# ui.net
KiCad netlist of a schematic drawn in EAGLE
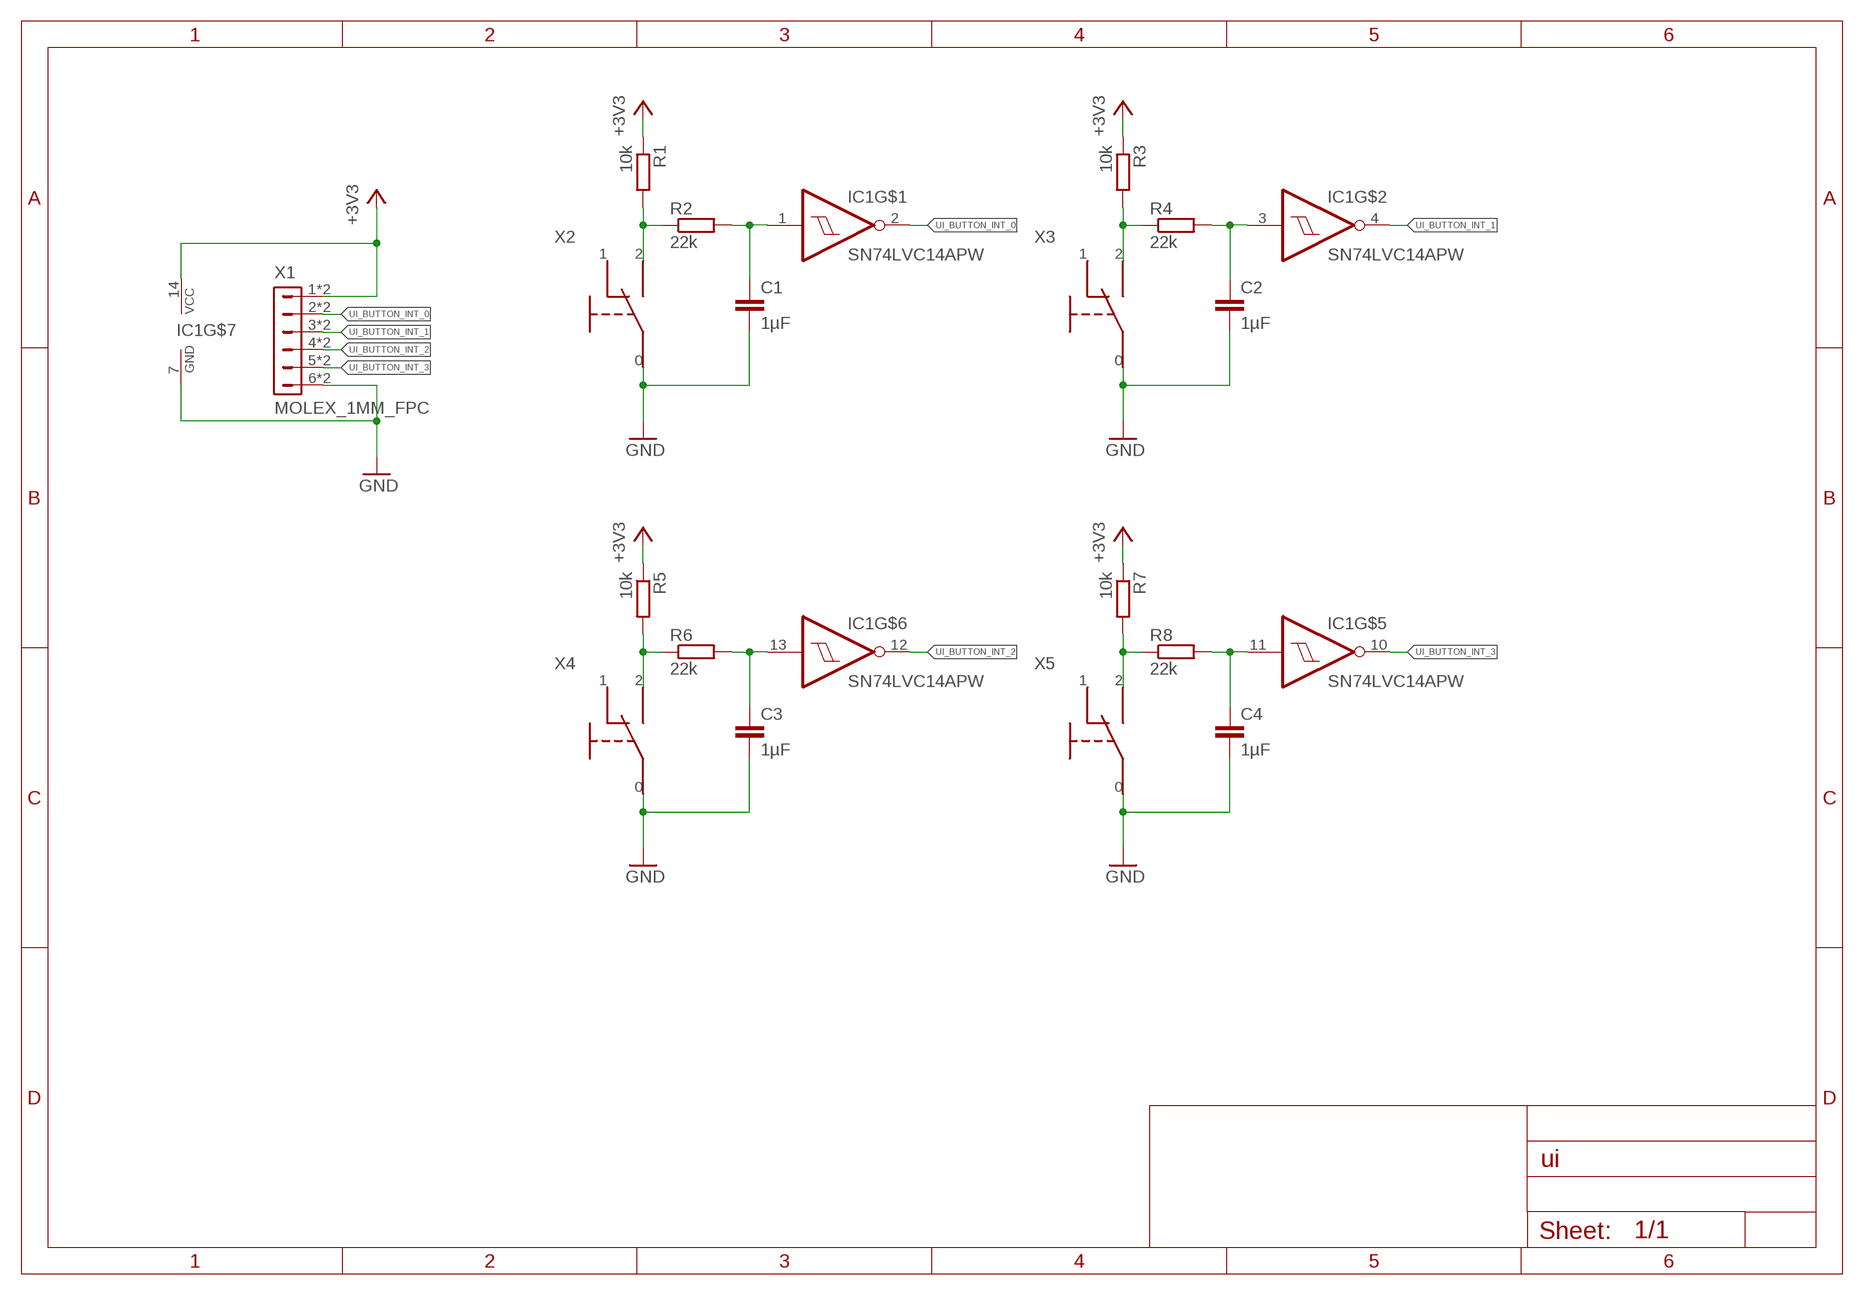
[diagram p0: schematic, sheet 1]

(export (version "E")
  (design (tool "Eeschema 10.0.6"))
  (components
    (comp (ref "C1")
      (value "1µF")
      (footprint "eagle-import:C0805")
      (libsource (lib "eagle-import") (part "C-EUC0805"))
    )
    (comp (ref "C2")
      (value "1µF")
      (footprint "eagle-import:C0805")
      (libsource (lib "eagle-import") (part "C-EUC0805"))
    )
    (comp (ref "C3")
      (value "1µF")
      (footprint "eagle-import:C0805")
      (libsource (lib "eagle-import") (part "C-EUC0805"))
    )
    (comp (ref "C4")
      (value "1µF")
      (footprint "eagle-import:C0805")
      (libsource (lib "eagle-import") (part "C-EUC0805"))
    )
    (comp (ref "IC1")
      (value "SN74LVC14APW")
      (footprint "eagle-import:TSSOP14")
      (fields (field (name "OC_MOUSER") "595-SN74LVC14APWR"))
      (libsource (lib "eagle-import") (part "SN74LVC14APW"))
    )
    (comp (ref "R1")
      (value "10k")
      (footprint "eagle-import:R0805")
      (libsource (lib "eagle-import") (part "R-EU_R0805"))
    )
    (comp (ref "R2")
      (value "22k")
      (footprint "eagle-import:R0805")
      (libsource (lib "eagle-import") (part "R-EU_R0805"))
    )
    (comp (ref "R3")
      (value "10k")
      (footprint "eagle-import:R0805")
      (libsource (lib "eagle-import") (part "R-EU_R0805"))
    )
    (comp (ref "R4")
      (value "22k")
      (footprint "eagle-import:R0805")
      (libsource (lib "eagle-import") (part "R-EU_R0805"))
    )
    (comp (ref "R5")
      (value "10k")
      (footprint "eagle-import:R0805")
      (libsource (lib "eagle-import") (part "R-EU_R0805"))
    )
    (comp (ref "R6")
      (value "22k")
      (footprint "eagle-import:R0805")
      (libsource (lib "eagle-import") (part "R-EU_R0805"))
    )
    (comp (ref "R7")
      (value "10k")
      (footprint "eagle-import:R0805")
      (libsource (lib "eagle-import") (part "R-EU_R0805"))
    )
    (comp (ref "R8")
      (value "22k")
      (footprint "eagle-import:R0805")
      (libsource (lib "eagle-import") (part "R-EU_R0805"))
    )
    (comp (ref "X1")
      (value "MOLEX_1MM_FPC")
      (footprint "eagle-import:1MM_FPC_ZIF")
      (libsource (lib "eagle-import") (part "MOLEX_1MM_FPC"))
    )
    (comp (ref "X2")
      (value "PVA2OAH11.7NV2")
      (footprint "eagle-import:BUTTON-2")
      (libsource (lib "eagle-import") (part "PVA2OAH11.7NV2"))
    )
    (comp (ref "X3")
      (value "PVA2OAH11.7NV2")
      (footprint "eagle-import:BUTTON-2")
      (libsource (lib "eagle-import") (part "PVA2OAH11.7NV2"))
    )
    (comp (ref "X4")
      (value "PVA2OAH11.7NV2")
      (footprint "eagle-import:BUTTON-2")
      (libsource (lib "eagle-import") (part "PVA2OAH11.7NV2"))
    )
    (comp (ref "X5")
      (value "PVA2OAH11.7NV2")
      (footprint "eagle-import:BUTTON-2")
      (libsource (lib "eagle-import") (part "PVA2OAH11.7NV2"))
    )
  )
  (nets
    (net (code "1") (name "+3V3") (class "Default")
      (node (ref "IC1") (pin "14") (pinfunction "VCC_14") (pintype "power_in"))
      (node (ref "R1") (pin "1") (pinfunction "1_1") (pintype "passive"))
      (node (ref "R3") (pin "1") (pinfunction "1_1") (pintype "passive"))
      (node (ref "R5") (pin "1") (pinfunction "1_1") (pintype "passive"))
      (node (ref "R7") (pin "1") (pinfunction "1_1") (pintype "passive"))
      (node (ref "X1") (pin "1") (pinfunction "1_1") (pintype "passive"))
      (node (ref "X1") (pin "7") (pinfunction "1_7") (pintype "passive"))
    )
    (net (code "2") (name "GND") (class "Default")
      (node (ref "C1") (pin "2") (pinfunction "2_2") (pintype "passive"))
      (node (ref "C2") (pin "2") (pinfunction "2_2") (pintype "passive"))
      (node (ref "C3") (pin "2") (pinfunction "2_2") (pintype "passive"))
      (node (ref "C4") (pin "2") (pinfunction "2_2") (pintype "passive"))
      (node (ref "IC1") (pin "7") (pinfunction "GND_7") (pintype "power_in"))
      (node (ref "X1") (pin "12") (pinfunction "6_12") (pintype "passive"))
      (node (ref "X1") (pin "6") (pinfunction "6_6") (pintype "passive"))
      (node (ref "X2") (pin "0") (pinfunction "0_0") (pintype "bidirectional"))
      (node (ref "X3") (pin "0") (pinfunction "0_0") (pintype "bidirectional"))
      (node (ref "X4") (pin "0") (pinfunction "0_0") (pintype "bidirectional"))
      (node (ref "X5") (pin "0") (pinfunction "0_0") (pintype "bidirectional"))
    )
    (net (code "3") (name "Net-(IC1A-I)") (class "Default")
      (node (ref "C1") (pin "1") (pinfunction "1_1") (pintype "passive"))
      (node (ref "IC1") (pin "1") (pinfunction "I_1") (pintype "input"))
      (node (ref "R2") (pin "2") (pinfunction "2_2") (pintype "passive"))
    )
    (net (code "4") (name "Net-(IC1B-I)") (class "Default")
      (node (ref "C2") (pin "1") (pinfunction "1_1") (pintype "passive"))
      (node (ref "IC1") (pin "3") (pinfunction "I_3") (pintype "input"))
      (node (ref "R4") (pin "2") (pinfunction "2_2") (pintype "passive"))
    )
    (net (code "5") (name "Net-(IC1E-I)") (class "Default")
      (node (ref "C4") (pin "1") (pinfunction "1_1") (pintype "passive"))
      (node (ref "IC1") (pin "11") (pinfunction "I_11") (pintype "input"))
      (node (ref "R8") (pin "2") (pinfunction "2_2") (pintype "passive"))
    )
    (net (code "6") (name "Net-(IC1F-I)") (class "Default")
      (node (ref "C3") (pin "1") (pinfunction "1_1") (pintype "passive"))
      (node (ref "IC1") (pin "13") (pinfunction "I_13") (pintype "input"))
      (node (ref "R6") (pin "2") (pinfunction "2_2") (pintype "passive"))
    )
    (net (code "7") (name "Net-(R1-Pad2)") (class "Default")
      (node (ref "R1") (pin "2") (pinfunction "2_2") (pintype "passive"))
      (node (ref "R2") (pin "1") (pinfunction "1_1") (pintype "passive"))
      (node (ref "X2") (pin "2") (pinfunction "2_2") (pintype "bidirectional"))
    )
    (net (code "8") (name "Net-(R3-Pad2)") (class "Default")
      (node (ref "R3") (pin "2") (pinfunction "2_2") (pintype "passive"))
      (node (ref "R4") (pin "1") (pinfunction "1_1") (pintype "passive"))
      (node (ref "X3") (pin "2") (pinfunction "2_2") (pintype "bidirectional"))
    )
    (net (code "9") (name "Net-(R5-Pad2)") (class "Default")
      (node (ref "R5") (pin "2") (pinfunction "2_2") (pintype "passive"))
      (node (ref "R6") (pin "1") (pinfunction "1_1") (pintype "passive"))
      (node (ref "X4") (pin "2") (pinfunction "2_2") (pintype "bidirectional"))
    )
    (net (code "10") (name "Net-(R7-Pad2)") (class "Default")
      (node (ref "R7") (pin "2") (pinfunction "2_2") (pintype "passive"))
      (node (ref "R8") (pin "1") (pinfunction "1_1") (pintype "passive"))
      (node (ref "X5") (pin "2") (pinfunction "2_2") (pintype "bidirectional"))
    )
    (net (code "11") (name "UI_BUTTON_INT_0") (class "Default")
      (node (ref "IC1") (pin "2") (pinfunction "O_2") (pintype "output"))
      (node (ref "X1") (pin "2") (pinfunction "2_2") (pintype "passive"))
      (node (ref "X1") (pin "8") (pinfunction "2_8") (pintype "passive"))
    )
    (net (code "12") (name "UI_BUTTON_INT_1") (class "Default")
      (node (ref "IC1") (pin "4") (pinfunction "O_4") (pintype "output"))
      (node (ref "X1") (pin "3") (pinfunction "3_3") (pintype "passive"))
      (node (ref "X1") (pin "9") (pinfunction "3_9") (pintype "passive"))
    )
    (net (code "13") (name "UI_BUTTON_INT_2") (class "Default")
      (node (ref "IC1") (pin "12") (pinfunction "O_12") (pintype "output"))
      (node (ref "X1") (pin "10") (pinfunction "4_10") (pintype "passive"))
      (node (ref "X1") (pin "4") (pinfunction "4_4") (pintype "passive"))
    )
    (net (code "14") (name "UI_BUTTON_INT_3") (class "Default")
      (node (ref "IC1") (pin "10") (pinfunction "O_10") (pintype "output"))
      (node (ref "X1") (pin "11") (pinfunction "5_11") (pintype "passive"))
      (node (ref "X1") (pin "5") (pinfunction "5_5") (pintype "passive"))
    )
    (net (code "15") (name "unconnected-(X2-Pad1)") (class "Default")
      (node (ref "X2") (pin "1") (pinfunction "1_1") (pintype "passive"))
    )
    (net (code "16") (name "unconnected-(X3-Pad1)") (class "Default")
      (node (ref "X3") (pin "1") (pinfunction "1_1") (pintype "passive"))
    )
    (net (code "17") (name "unconnected-(X4-Pad1)") (class "Default")
      (node (ref "X4") (pin "1") (pinfunction "1_1") (pintype "passive"))
    )
    (net (code "18") (name "unconnected-(X5-Pad1)") (class "Default")
      (node (ref "X5") (pin "1") (pinfunction "1_1") (pintype "passive"))
    )
  )
)
